# Wio_Node_v1_0.net
KiCad netlist of a schematic drawn in EAGLE
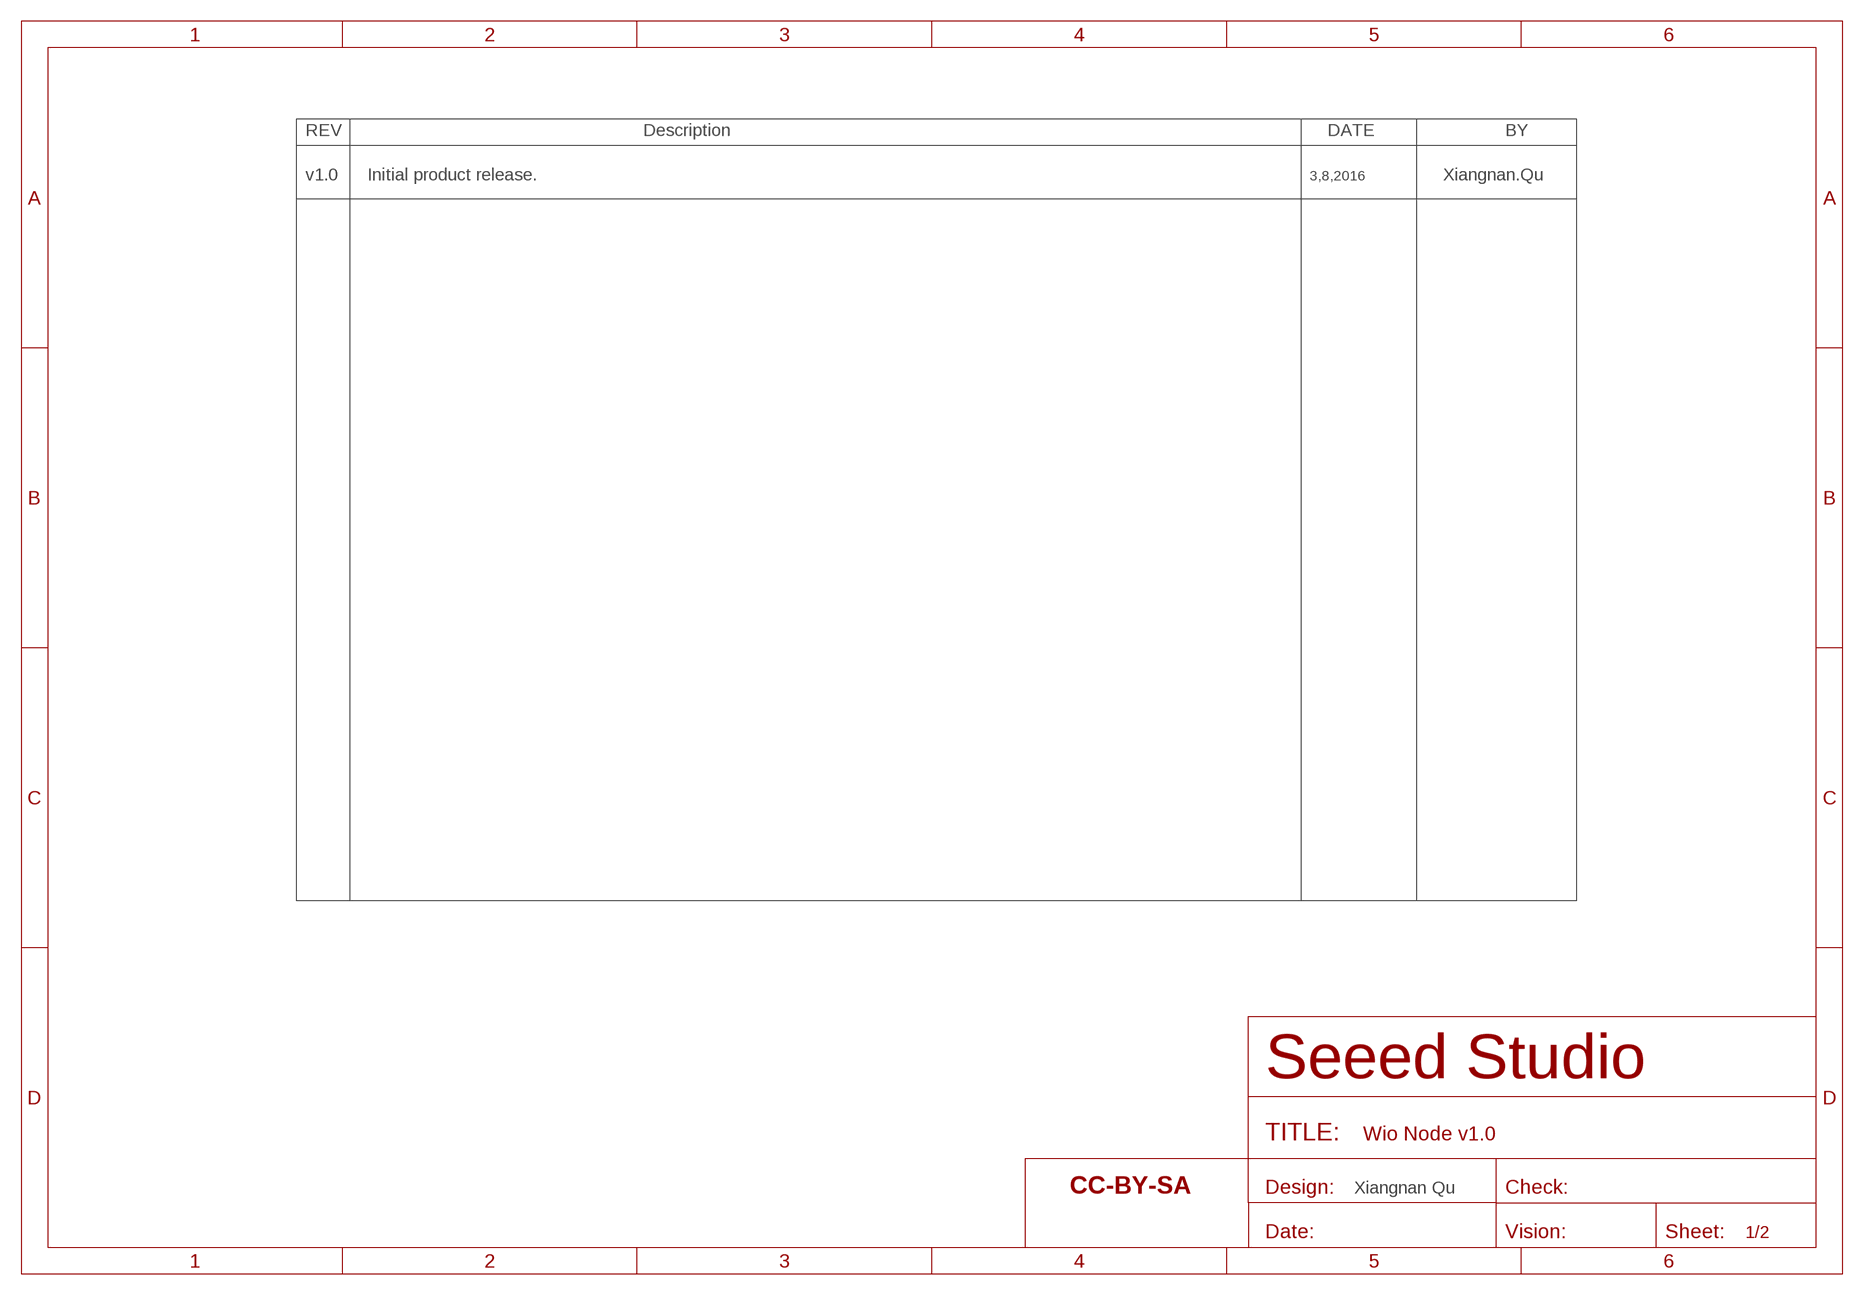
[diagram p0: schematic, sheet 1]
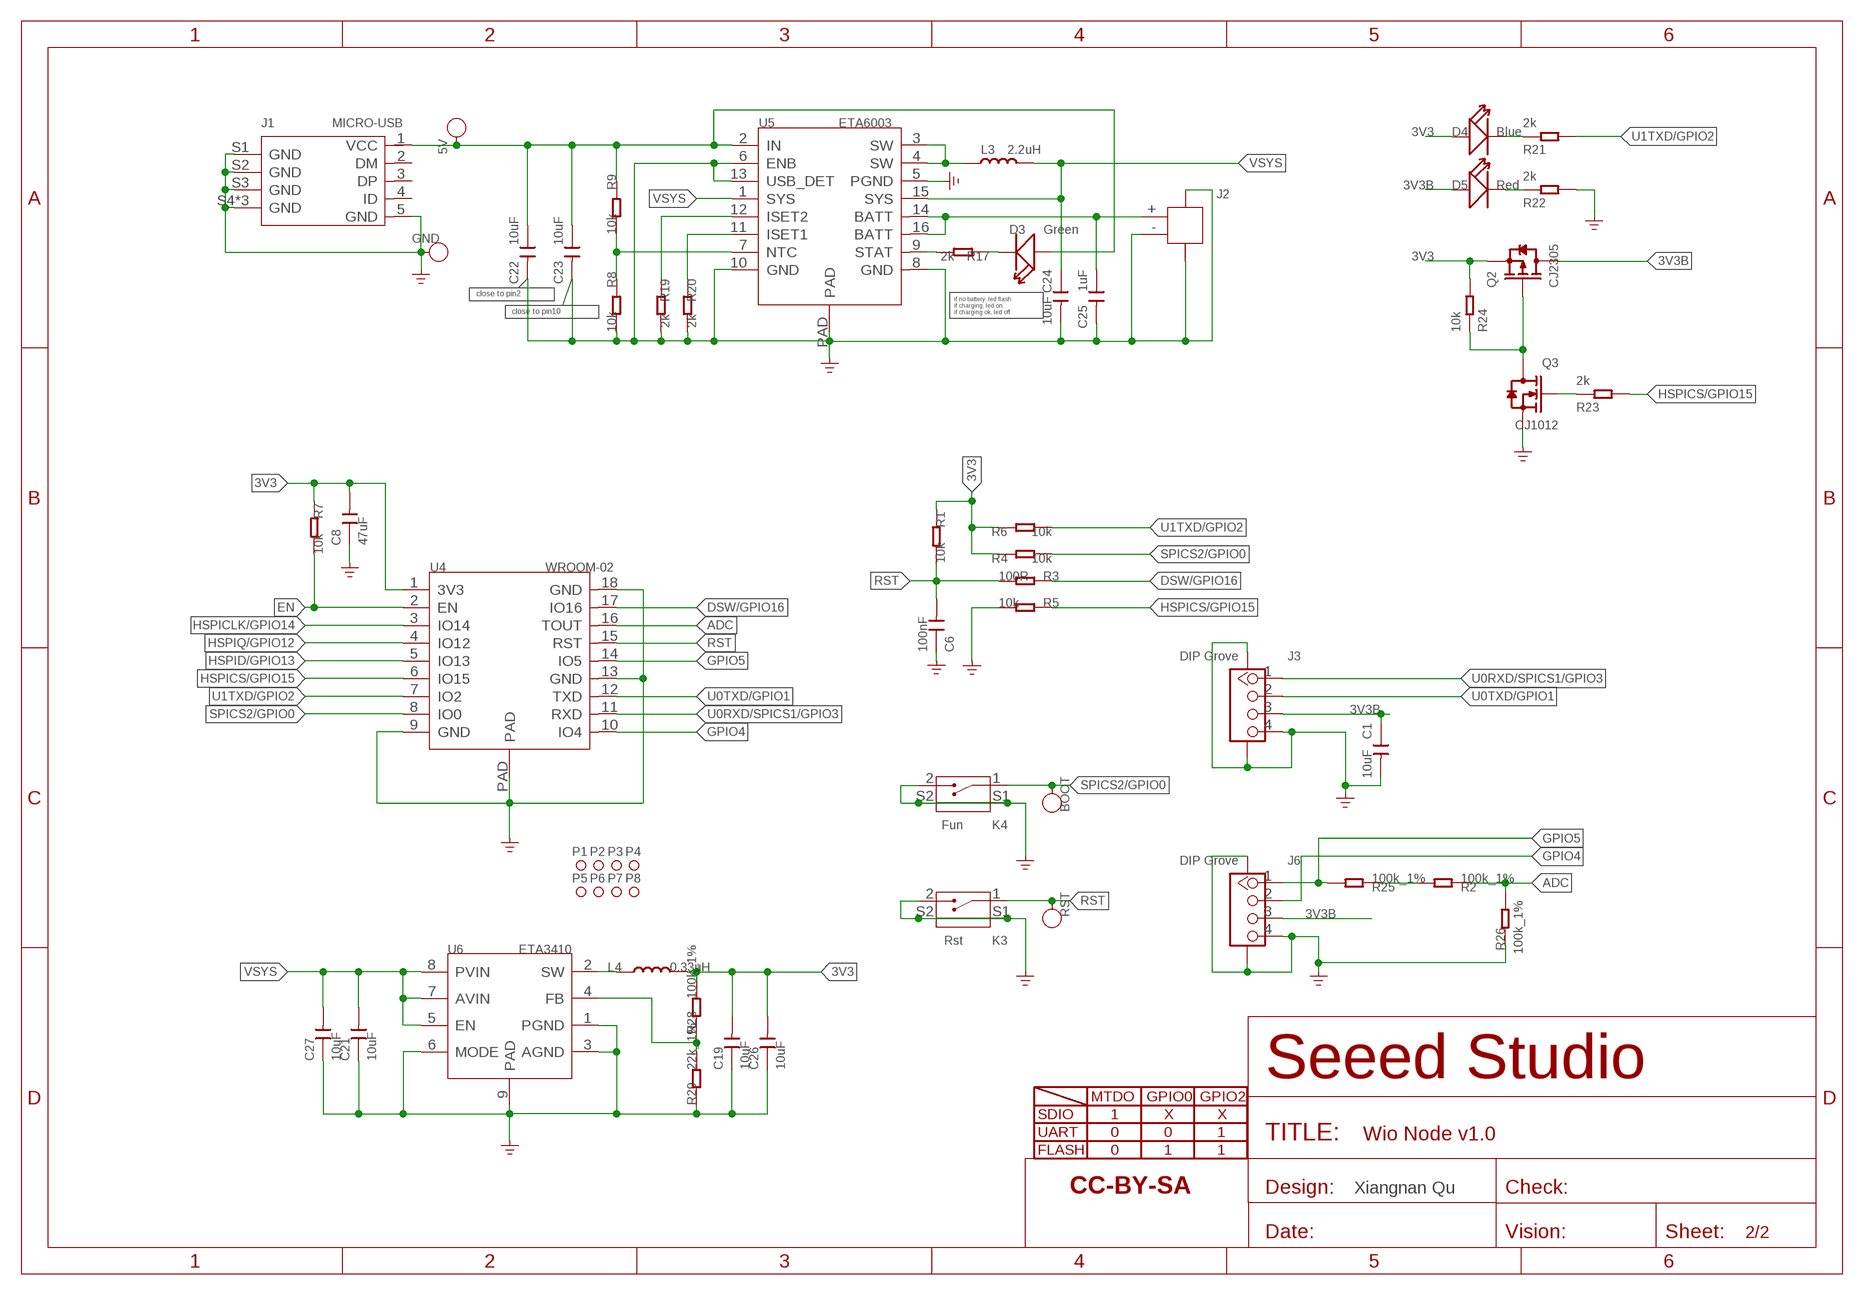
[diagram p1: schematic, sheet 2]

(export (version "E")
  (design (tool "Eeschema 10.0.6"))
  (components
    (comp (ref "5V")
      (value "TEST-POINT'4545'")
      (footprint "eagle-import:TP-D45MIL")
      (fields (field (name "PARTNO") "DNP"))
      (libsource (lib "eagle-import") (part "TEST-POINT'4545'"))
    )
    (comp (ref "BOOT")
      (value "TEST-POINT'4545'")
      (footprint "eagle-import:TP-D45MIL")
      (fields (field (name "PARTNO") "DNP"))
      (libsource (lib "eagle-import") (part "TEST-POINT'4545'"))
    )
    (comp (ref "C1")
      (value "10uF")
      (footprint "eagle-import:C0402")
      (libsource (lib "eagle-import") (part "CAP-0402"))
    )
    (comp (ref "C6")
      (value "100nF")
      (footprint "eagle-import:C0201")
      (libsource (lib "eagle-import") (part "CAP-0201"))
    )
    (comp (ref "C8")
      (value "47uF")
      (footprint "eagle-import:C0805")
      (libsource (lib "eagle-import") (part "CAP-0805"))
    )
    (comp (ref "C19")
      (value "10uF")
      (footprint "eagle-import:C0402")
      (libsource (lib "eagle-import") (part "CAP-0402"))
    )
    (comp (ref "C21")
      (value "10uF")
      (footprint "eagle-import:C0402")
      (libsource (lib "eagle-import") (part "CAP-0402"))
    )
    (comp (ref "C22")
      (value "10uF")
      (footprint "eagle-import:C0805")
      (libsource (lib "eagle-import") (part "CAP-0805"))
    )
    (comp (ref "C23")
      (value "10uF")
      (footprint "eagle-import:C0402")
      (libsource (lib "eagle-import") (part "CAP-0402"))
    )
    (comp (ref "C24")
      (value "10uF")
      (footprint "eagle-import:C0402")
      (libsource (lib "eagle-import") (part "CAP-0402"))
    )
    (comp (ref "C25")
      (value "1uF")
      (footprint "eagle-import:C0402")
      (libsource (lib "eagle-import") (part "CAP-0402"))
    )
    (comp (ref "C26")
      (value "10uF")
      (footprint "eagle-import:C0402")
      (libsource (lib "eagle-import") (part "CAP-0402"))
    )
    (comp (ref "C27")
      (value "10uF")
      (footprint "eagle-import:C0402")
      (libsource (lib "eagle-import") (part "CAP-0402"))
    )
    (comp (ref "D3")
      (value "Green")
      (footprint "eagle-import:LED-0402")
      (libsource (lib "eagle-import") (part "LED-0402"))
    )
    (comp (ref "D4")
      (value "Blue")
      (footprint "eagle-import:LED-0402")
      (libsource (lib "eagle-import") (part "LED-0402"))
    )
    (comp (ref "D5")
      (value "Red")
      (footprint "eagle-import:LED-0402")
      (libsource (lib "eagle-import") (part "LED-0402"))
    )
    (comp (ref "FR1")
      (value "SEEEDSTUDIO-OPEN-SCH-FRAME")
      (footprint "eagle-import:SEEEDSTUDIO-PCB-FRAME")
      (libsource (lib "eagle-import") (part "SEEEDSTUDIO-OPEN-SCH-FRAME"))
    )
    (comp (ref "GND")
      (value "TEST-POINT'4545'")
      (footprint "eagle-import:TP-D45MIL")
      (fields (field (name "PARTNO") "DNP"))
      (libsource (lib "eagle-import") (part "TEST-POINT'4545'"))
    )
    (comp (ref "J1")
      (value "MICRO-USB")
      (footprint "eagle-import:MICRO-USB5+4P-SMD-0.65-B")
      (libsource (lib "eagle-import") (part "MICRO-USB5+4P'5+4P'"))
    )
    (comp (ref "J2")
      (value "JST-2P-SMD'2.0'")
      (footprint "eagle-import:HW2-SMD-2.0-90D")
      (libsource (lib "eagle-import") (part "JST-2P-SMD'2.0'"))
    )
    (comp (ref "J3")
      (value "DIP Grove")
      (footprint "eagle-import:HW4-SMD-2.0-90D")
      (libsource (lib "eagle-import") (part "GROVE-CONNECTOR-SMD'90D'"))
    )
    (comp (ref "J6")
      (value "DIP Grove")
      (footprint "eagle-import:HW4-SMD-2.0-90D")
      (libsource (lib "eagle-import") (part "GROVE-CONNECTOR-SMD'90D'"))
    )
    (comp (ref "K3")
      (value "Rst")
      (footprint "eagle-import:SW4-SMD-4.5X3.8X1.8MM-90D")
      (libsource (lib "eagle-import") (part "BUTTON-2+2P'HQ-TP-1100A'"))
    )
    (comp (ref "K4")
      (value "Fun")
      (footprint "eagle-import:SW4-SMD-4.5X3.8X1.8MM-90D")
      (libsource (lib "eagle-import") (part "BUTTON-2+2P'HQ-TP-1100A'"))
    )
    (comp (ref "L3")
      (value "2.2uH")
      (footprint "eagle-import:L0805")
      (libsource (lib "eagle-import") (part "INDUCTOR/FERRITE-BEAD'0805'"))
    )
    (comp (ref "L4")
      (value "0.33uH")
      (footprint "eagle-import:L201610")
      (libsource (lib "eagle-import") (part "L-MPM201610SR33_T"))
    )
    (comp (ref "P1")
      (value "MARK-1.0'ANNULAR'")
      (footprint "eagle-import:ROUND-MARK-1.0")
      (fields (field (name "PARTNO") "DNP"))
      (libsource (lib "eagle-import") (part "MARK-1.0'ANNULAR'"))
    )
    (comp (ref "P2")
      (value "MARK-1.0'ANNULAR'")
      (footprint "eagle-import:ROUND-MARK-1.0")
      (fields (field (name "PARTNO") "DNP"))
      (libsource (lib "eagle-import") (part "MARK-1.0'ANNULAR'"))
    )
    (comp (ref "P3")
      (value "MARK-1.0'ANNULAR'")
      (footprint "eagle-import:ROUND-MARK-1.0")
      (fields (field (name "PARTNO") "DNP"))
      (libsource (lib "eagle-import") (part "MARK-1.0'ANNULAR'"))
    )
    (comp (ref "P4")
      (value "MARK-1.0'ANNULAR'")
      (footprint "eagle-import:ROUND-MARK-1.0")
      (fields (field (name "PARTNO") "DNP"))
      (libsource (lib "eagle-import") (part "MARK-1.0'ANNULAR'"))
    )
    (comp (ref "P5")
      (value "MARK-1.0'ANNULAR'")
      (footprint "eagle-import:ROUND-MARK-1.0")
      (fields (field (name "PARTNO") "DNP"))
      (libsource (lib "eagle-import") (part "MARK-1.0'ANNULAR'"))
    )
    (comp (ref "P6")
      (value "MARK-1.0'ANNULAR'")
      (footprint "eagle-import:ROUND-MARK-1.0")
      (fields (field (name "PARTNO") "DNP"))
      (libsource (lib "eagle-import") (part "MARK-1.0'ANNULAR'"))
    )
    (comp (ref "P7")
      (value "MARK-1.0'ANNULAR'")
      (footprint "eagle-import:ROUND-MARK-1.0")
      (fields (field (name "PARTNO") "DNP"))
      (libsource (lib "eagle-import") (part "MARK-1.0'ANNULAR'"))
    )
    (comp (ref "P8")
      (value "MARK-1.0'ANNULAR'")
      (footprint "eagle-import:ROUND-MARK-1.0")
      (fields (field (name "PARTNO") "DNP"))
      (libsource (lib "eagle-import") (part "MARK-1.0'ANNULAR'"))
    )
    (comp (ref "Q2")
      (value "CJ2305")
      (footprint "eagle-import:SOT-23")
      (libsource (lib "eagle-import") (part "MOSFET-P'SI2323CDS/SI2305DS{lt}BR{gt}'"))
    )
    (comp (ref "Q3")
      (value "CJ1012")
      (footprint "eagle-import:SOT-523")
      (libsource (lib "eagle-import") (part "MOSFET-N+"))
    )
    (comp (ref "R1")
      (value "10k")
      (footprint "eagle-import:R0201")
      (libsource (lib "eagle-import") (part "RES-0201"))
    )
    (comp (ref "R2")
      (value "100k_1%")
      (footprint "eagle-import:R0201")
      (libsource (lib "eagle-import") (part "RES-0201"))
    )
    (comp (ref "R3")
      (value "100R")
      (footprint "eagle-import:R0201")
      (libsource (lib "eagle-import") (part "RES-0201"))
    )
    (comp (ref "R4")
      (value "10k")
      (footprint "eagle-import:R0201")
      (libsource (lib "eagle-import") (part "RES-0201"))
    )
    (comp (ref "R5")
      (value "10k")
      (footprint "eagle-import:R0201")
      (libsource (lib "eagle-import") (part "RES-0201"))
    )
    (comp (ref "R6")
      (value "10k")
      (footprint "eagle-import:R0201")
      (libsource (lib "eagle-import") (part "RES-0201"))
    )
    (comp (ref "R7")
      (value "10k")
      (footprint "eagle-import:R0201")
      (libsource (lib "eagle-import") (part "RES-0201"))
    )
    (comp (ref "R8")
      (value "10k")
      (footprint "eagle-import:R0201")
      (libsource (lib "eagle-import") (part "RES-0201"))
    )
    (comp (ref "R9")
      (value "10k")
      (footprint "eagle-import:R0201")
      (libsource (lib "eagle-import") (part "RES-0201"))
    )
    (comp (ref "R17")
      (value "2k")
      (footprint "eagle-import:R0201")
      (libsource (lib "eagle-import") (part "RES-0201"))
    )
    (comp (ref "R19")
      (value "2k")
      (footprint "eagle-import:R0201")
      (libsource (lib "eagle-import") (part "RES-0201"))
    )
    (comp (ref "R20")
      (value "2k")
      (footprint "eagle-import:R0201")
      (libsource (lib "eagle-import") (part "RES-0201"))
    )
    (comp (ref "R21")
      (value "2k")
      (footprint "eagle-import:R0201")
      (libsource (lib "eagle-import") (part "RES-0201"))
    )
    (comp (ref "R22")
      (value "2k")
      (footprint "eagle-import:R0201")
      (libsource (lib "eagle-import") (part "RES-0201"))
    )
    (comp (ref "R23")
      (value "2k")
      (footprint "eagle-import:R0201")
      (libsource (lib "eagle-import") (part "RES-0201"))
    )
    (comp (ref "R24")
      (value "10k")
      (footprint "eagle-import:R0201")
      (libsource (lib "eagle-import") (part "RES-0201"))
    )
    (comp (ref "R25")
      (value "100k_1%")
      (footprint "eagle-import:R0201")
      (libsource (lib "eagle-import") (part "RES-0201"))
    )
    (comp (ref "R26")
      (value "100k_1%")
      (footprint "eagle-import:R0201")
      (libsource (lib "eagle-import") (part "RES-0201"))
    )
    (comp (ref "R28")
      (value "100k_1%")
      (footprint "eagle-import:R0201")
      (libsource (lib "eagle-import") (part "RES-0201"))
    )
    (comp (ref "R29")
      (value "22k_1%")
      (footprint "eagle-import:R0402")
      (libsource (lib "eagle-import") (part "RES-0402"))
    )
    (comp (ref "RST")
      (value "TEST-POINT'4545'")
      (footprint "eagle-import:TP-D45MIL")
      (fields (field (name "PARTNO") "DNP"))
      (libsource (lib "eagle-import") (part "TEST-POINT'4545'"))
    )
    (comp (ref "U4")
      (value "WROOM-02")
      (footprint "eagle-import:ESP18-SMD-1.5-18X20MM")
      (libsource (lib "eagle-import") (part "MOUDLE-WIFI-ESP-WROOM-02"))
    )
    (comp (ref "U5")
      (value "ETA6003")
      (footprint "eagle-import:QFN16G-0.5-3X3MM")
      (libsource (lib "eagle-import") (part "PMIC-ETA6003"))
    )
    (comp (ref "U6")
      (value "ETA3410")
      (footprint "eagle-import:DFN8G-0.5-2X2MM")
      (libsource (lib "eagle-import") (part "CONVERTER-ETA3410"))
    )
    (comp (ref "FR4")
      (value "SEEEDSTUDIO-OPEN-SCH-FRAME")
      (footprint "eagle-import:SEEEDSTUDIO-PCB-FRAME")
      (libsource (lib "eagle-import") (part "SEEEDSTUDIO-OPEN-SCH-FRAME"))
    )
  )
  (nets
    (net (code "1") (name "3V3") (class "Default")
      (node (ref "C19") (pin "2") (pinfunction "2_2") (pintype "passive"))
      (node (ref "C26") (pin "2") (pinfunction "2_2") (pintype "passive"))
      (node (ref "C8") (pin "2") (pinfunction "2_2") (pintype "passive"))
      (node (ref "D4") (pin "+") (pinfunction "+_+") (pintype "passive"))
      (node (ref "L4") (pin "2") (pinfunction "2_2") (pintype "passive"))
      (node (ref "Q2") (pin "2") (pinfunction "S_2") (pintype "passive"))
      (node (ref "R1") (pin "1") (pinfunction "1_1") (pintype "passive"))
      (node (ref "R24") (pin "2") (pinfunction "2_2") (pintype "passive"))
      (node (ref "R28") (pin "2") (pinfunction "2_2") (pintype "passive"))
      (node (ref "R4") (pin "1") (pinfunction "1_1") (pintype "passive"))
      (node (ref "R6") (pin "1") (pinfunction "1_1") (pintype "passive"))
      (node (ref "R7") (pin "1") (pinfunction "1_1") (pintype "passive"))
      (node (ref "U4") (pin "1") (pinfunction "3V3_1") (pintype "bidirectional"))
    )
    (net (code "2") (name "3V3B") (class "Default")
      (node (ref "C1") (pin "1") (pinfunction "1_1") (pintype "passive"))
      (node (ref "D5") (pin "+") (pinfunction "+_+") (pintype "passive"))
      (node (ref "J3") (pin "3") (pinfunction "3_3") (pintype "bidirectional"))
      (node (ref "J6") (pin "3") (pinfunction "3_3") (pintype "bidirectional"))
      (node (ref "Q2") (pin "3") (pinfunction "D_3") (pintype "passive"))
    )
    (net (code "3") (name "ADC") (class "Default")
      (node (ref "R2") (pin "1") (pinfunction "1_1") (pintype "passive"))
      (node (ref "R26") (pin "2") (pinfunction "2_2") (pintype "passive"))
      (node (ref "U4") (pin "16") (pinfunction "TOUT_16") (pintype "bidirectional"))
    )
    (net (code "4") (name "DSW{slash}GPIO16") (class "Default")
      (node (ref "R3") (pin "1") (pinfunction "1_1") (pintype "passive"))
      (node (ref "U4") (pin "17") (pinfunction "IO16_17") (pintype "bidirectional"))
    )
    (net (code "5") (name "EN") (class "Default")
      (node (ref "R7") (pin "2") (pinfunction "2_2") (pintype "passive"))
      (node (ref "U4") (pin "2") (pinfunction "EN_2") (pintype "bidirectional"))
    )
    (net (code "6") (name "GND") (class "Default")
      (node (ref "C1") (pin "2") (pinfunction "2_2") (pintype "passive"))
      (node (ref "C19") (pin "1") (pinfunction "1_1") (pintype "passive"))
      (node (ref "C21") (pin "1") (pinfunction "1_1") (pintype "passive"))
      (node (ref "C22") (pin "2") (pinfunction "2_2") (pintype "passive"))
      (node (ref "C23") (pin "2") (pinfunction "2_2") (pintype "passive"))
      (node (ref "C24") (pin "2") (pinfunction "2_2") (pintype "passive"))
      (node (ref "C25") (pin "2") (pinfunction "2_2") (pintype "passive"))
      (node (ref "C26") (pin "1") (pinfunction "1_1") (pintype "passive"))
      (node (ref "C27") (pin "1") (pinfunction "1_1") (pintype "passive"))
      (node (ref "C6") (pin "1") (pinfunction "1_1") (pintype "passive"))
      (node (ref "C8") (pin "1") (pinfunction "1_1") (pintype "passive"))
      (node (ref "GND") (pin "T") (pinfunction "T_T") (pintype "bidirectional"))
      (node (ref "J1") (pin "5") (pinfunction "GND_5") (pintype "bidirectional"))
      (node (ref "J1") (pin "S1") (pinfunction "GND_S1") (pintype "bidirectional"))
      (node (ref "J1") (pin "S2") (pinfunction "GND_S2") (pintype "bidirectional"))
      (node (ref "J1") (pin "S3") (pinfunction "GND_S3") (pintype "bidirectional"))
      (node (ref "J1") (pin "S4") (pinfunction "GND_S4") (pintype "bidirectional"))
      (node (ref "J1") (pin "S5") (pinfunction "GND_S5") (pintype "bidirectional"))
      (node (ref "J1") (pin "S6") (pinfunction "GND_S6") (pintype "bidirectional"))
      (node (ref "J2") (pin "-") (pinfunction "2_-") (pintype "bidirectional"))
      (node (ref "J2") (pin "3") (pinfunction "3_3") (pintype "bidirectional"))
      (node (ref "J2") (pin "4") (pinfunction "4_4") (pintype "bidirectional"))
      (node (ref "J3") (pin "4") (pinfunction "4_4") (pintype "bidirectional"))
      (node (ref "J3") (pin "SS1") (pinfunction "SS1_SS1") (pintype "bidirectional"))
      (node (ref "J3") (pin "SS2") (pinfunction "SS2_SS2") (pintype "bidirectional"))
      (node (ref "J6") (pin "4") (pinfunction "4_4") (pintype "bidirectional"))
      (node (ref "J6") (pin "SS1") (pinfunction "SS1_SS1") (pintype "bidirectional"))
      (node (ref "J6") (pin "SS2") (pinfunction "SS2_SS2") (pintype "bidirectional"))
      (node (ref "K3") (pin "2") (pinfunction "2_2") (pintype "bidirectional"))
      (node (ref "K3") (pin "S1") (pinfunction "S1_S1") (pintype "bidirectional"))
      (node (ref "K3") (pin "S2") (pinfunction "S2_S2") (pintype "bidirectional"))
      (node (ref "K4") (pin "2") (pinfunction "2_2") (pintype "bidirectional"))
      (node (ref "K4") (pin "S1") (pinfunction "S1_S1") (pintype "bidirectional"))
      (node (ref "K4") (pin "S2") (pinfunction "S2_S2") (pintype "bidirectional"))
      (node (ref "Q3") (pin "2") (pinfunction "S_2") (pintype "passive"))
      (node (ref "R19") (pin "2") (pinfunction "2_2") (pintype "passive"))
      (node (ref "R20") (pin "2") (pinfunction "2_2") (pintype "passive"))
      (node (ref "R22") (pin "2") (pinfunction "2_2") (pintype "passive"))
      (node (ref "R26") (pin "1") (pinfunction "1_1") (pintype "passive"))
      (node (ref "R29") (pin "1") (pinfunction "1_1") (pintype "passive"))
      (node (ref "R5") (pin "2") (pinfunction "2_2") (pintype "passive"))
      (node (ref "R8") (pin "2") (pinfunction "2_2") (pintype "passive"))
      (node (ref "U4") (pin "13") (pinfunction "GND_13") (pintype "bidirectional"))
      (node (ref "U4") (pin "18") (pinfunction "GND_18") (pintype "bidirectional"))
      (node (ref "U4") (pin "9") (pinfunction "GND_9") (pintype "bidirectional"))
      (node (ref "U4") (pin "PAD") (pinfunction "PAD_PAD") (pintype "bidirectional"))
      (node (ref "U5") (pin "10") (pinfunction "GND_10") (pintype "bidirectional"))
      (node (ref "U5") (pin "13") (pinfunction "USB_DET_13") (pintype "bidirectional"))
      (node (ref "U5") (pin "5") (pinfunction "PGND_5") (pintype "bidirectional"))
      (node (ref "U5") (pin "6") (pinfunction "ENB_6") (pintype "bidirectional"))
      (node (ref "U5") (pin "8") (pinfunction "GND_8") (pintype "bidirectional"))
      (node (ref "U5") (pin "PAD") (pinfunction "PAD_PAD") (pintype "bidirectional"))
      (node (ref "U6") (pin "1") (pinfunction "PGND_1") (pintype "bidirectional"))
      (node (ref "U6") (pin "3") (pinfunction "AGND_3") (pintype "bidirectional"))
      (node (ref "U6") (pin "6") (pinfunction "MODE_6") (pintype "bidirectional"))
      (node (ref "U6") (pin "9") (pinfunction "PAD_9") (pintype "bidirectional"))
    )
    (net (code "7") (name "GPIO4") (class "Default")
      (node (ref "J6") (pin "2") (pinfunction "2_2") (pintype "bidirectional"))
      (node (ref "U4") (pin "10") (pinfunction "IO4_10") (pintype "bidirectional"))
    )
    (net (code "8") (name "GPIO5") (class "Default")
      (node (ref "J6") (pin "1") (pinfunction "1_1") (pintype "bidirectional"))
      (node (ref "R25") (pin "2") (pinfunction "2_2") (pintype "passive"))
      (node (ref "U4") (pin "14") (pinfunction "IO5_14") (pintype "bidirectional"))
    )
    (net (code "9") (name "HSPICLK{slash}GPIO14") (class "Default")
      (node (ref "U4") (pin "3") (pinfunction "IO14_3") (pintype "bidirectional"))
    )
    (net (code "10") (name "HSPICS{slash}GPIO15") (class "Default")
      (node (ref "R23") (pin "2") (pinfunction "2_2") (pintype "passive"))
      (node (ref "R5") (pin "1") (pinfunction "1_1") (pintype "passive"))
      (node (ref "U4") (pin "6") (pinfunction "IO15_6") (pintype "bidirectional"))
    )
    (net (code "11") (name "HSPID{slash}GPIO13") (class "Default")
      (node (ref "U4") (pin "5") (pinfunction "IO13_5") (pintype "bidirectional"))
    )
    (net (code "12") (name "HSPIQ{slash}GPIO12") (class "Default")
      (node (ref "U4") (pin "4") (pinfunction "IO12_4") (pintype "bidirectional"))
    )
    (net (code "13") (name "Net-(D3-Pad-)") (class "Default")
      (node (ref "D3") (pin "-") (pinfunction "-_-") (pintype "passive"))
      (node (ref "R17") (pin "1") (pinfunction "1_1") (pintype "passive"))
    )
    (net (code "14") (name "Net-(D4-Pad-)") (class "Default")
      (node (ref "D4") (pin "-") (pinfunction "-_-") (pintype "passive"))
      (node (ref "R21") (pin "1") (pinfunction "1_1") (pintype "passive"))
    )
    (net (code "15") (name "Net-(D5-Pad-)") (class "Default")
      (node (ref "D5") (pin "-") (pinfunction "-_-") (pintype "passive"))
      (node (ref "R22") (pin "1") (pinfunction "1_1") (pintype "passive"))
    )
    (net (code "16") (name "Net-(J1-VCC)") (class "Default")
      (node (ref "5V") (pin "T") (pinfunction "T_T") (pintype "bidirectional"))
      (node (ref "C22") (pin "1") (pinfunction "1_1") (pintype "passive"))
      (node (ref "C23") (pin "1") (pinfunction "1_1") (pintype "passive"))
      (node (ref "D3") (pin "+") (pinfunction "+_+") (pintype "passive"))
      (node (ref "J1") (pin "1") (pinfunction "VCC_1") (pintype "bidirectional"))
      (node (ref "R9") (pin "1") (pinfunction "1_1") (pintype "passive"))
      (node (ref "U5") (pin "2") (pinfunction "IN_2") (pintype "bidirectional"))
    )
    (net (code "17") (name "Net-(J2-1)") (class "Default")
      (node (ref "C25") (pin "1") (pinfunction "1_1") (pintype "passive"))
      (node (ref "J2") (pin "+") (pinfunction "1_+") (pintype "bidirectional"))
      (node (ref "U5") (pin "14") (pinfunction "BATT_14") (pintype "bidirectional"))
      (node (ref "U5") (pin "16") (pinfunction "BATT_16") (pintype "bidirectional"))
    )
    (net (code "18") (name "Net-(L3-Pad1)") (class "Default")
      (node (ref "L3") (pin "1") (pinfunction "1_1") (pintype "passive"))
      (node (ref "U5") (pin "3") (pinfunction "SW_3") (pintype "bidirectional"))
      (node (ref "U5") (pin "4") (pinfunction "SW_4") (pintype "bidirectional"))
    )
    (net (code "19") (name "Net-(Q2-G)") (class "Default")
      (node (ref "Q2") (pin "1") (pinfunction "G_1") (pintype "passive"))
      (node (ref "Q3") (pin "3") (pinfunction "D_3") (pintype "passive"))
      (node (ref "R24") (pin "1") (pinfunction "1_1") (pintype "passive"))
    )
    (net (code "20") (name "Net-(Q3-G)") (class "Default")
      (node (ref "Q3") (pin "1") (pinfunction "G_1") (pintype "passive"))
      (node (ref "R23") (pin "1") (pinfunction "1_1") (pintype "passive"))
    )
    (net (code "21") (name "Net-(R2-Pad2)") (class "Default")
      (node (ref "R2") (pin "2") (pinfunction "2_2") (pintype "passive"))
      (node (ref "R25") (pin "1") (pinfunction "1_1") (pintype "passive"))
    )
    (net (code "22") (name "Net-(U5-ISET1)") (class "Default")
      (node (ref "R20") (pin "1") (pinfunction "1_1") (pintype "passive"))
      (node (ref "U5") (pin "11") (pinfunction "ISET1_11") (pintype "bidirectional"))
    )
    (net (code "23") (name "Net-(U5-ISET2)") (class "Default")
      (node (ref "R19") (pin "1") (pinfunction "1_1") (pintype "passive"))
      (node (ref "U5") (pin "12") (pinfunction "ISET2_12") (pintype "bidirectional"))
    )
    (net (code "24") (name "Net-(U5-NTC)") (class "Default")
      (node (ref "R8") (pin "1") (pinfunction "1_1") (pintype "passive"))
      (node (ref "R9") (pin "2") (pinfunction "2_2") (pintype "passive"))
      (node (ref "U5") (pin "7") (pinfunction "NTC_7") (pintype "bidirectional"))
    )
    (net (code "25") (name "Net-(U5-STAT)") (class "Default")
      (node (ref "R17") (pin "2") (pinfunction "2_2") (pintype "passive"))
      (node (ref "U5") (pin "9") (pinfunction "STAT_9") (pintype "bidirectional"))
    )
    (net (code "26") (name "Net-(U6-FB)") (class "Default")
      (node (ref "R28") (pin "1") (pinfunction "1_1") (pintype "passive"))
      (node (ref "R29") (pin "2") (pinfunction "2_2") (pintype "passive"))
      (node (ref "U6") (pin "4") (pinfunction "FB_4") (pintype "bidirectional"))
    )
    (net (code "27") (name "Net-(U6-SW)") (class "Default")
      (node (ref "L4") (pin "1") (pinfunction "1_1") (pintype "passive"))
      (node (ref "U6") (pin "2") (pinfunction "SW_2") (pintype "bidirectional"))
    )
    (net (code "28") (name "RST") (class "Default")
      (node (ref "C6") (pin "2") (pinfunction "2_2") (pintype "passive"))
      (node (ref "K3") (pin "1") (pinfunction "1_1") (pintype "bidirectional"))
      (node (ref "R1") (pin "2") (pinfunction "2_2") (pintype "passive"))
      (node (ref "R3") (pin "2") (pinfunction "2_2") (pintype "passive"))
      (node (ref "RST") (pin "T") (pinfunction "T_T") (pintype "bidirectional"))
      (node (ref "U4") (pin "15") (pinfunction "RST_15") (pintype "bidirectional"))
    )
    (net (code "29") (name "SPICS2{slash}GPIO0") (class "Default")
      (node (ref "BOOT") (pin "T") (pinfunction "T_T") (pintype "bidirectional"))
      (node (ref "K4") (pin "1") (pinfunction "1_1") (pintype "bidirectional"))
      (node (ref "R4") (pin "2") (pinfunction "2_2") (pintype "passive"))
      (node (ref "U4") (pin "8") (pinfunction "IO0_8") (pintype "bidirectional"))
    )
    (net (code "30") (name "U0RXD{slash}SPICS1{slash}GPIO3") (class "Default")
      (node (ref "J3") (pin "1") (pinfunction "1_1") (pintype "bidirectional"))
      (node (ref "U4") (pin "11") (pinfunction "RXD_11") (pintype "bidirectional"))
    )
    (net (code "31") (name "U0TXD{slash}GPIO1") (class "Default")
      (node (ref "J3") (pin "2") (pinfunction "2_2") (pintype "bidirectional"))
      (node (ref "U4") (pin "12") (pinfunction "TXD_12") (pintype "bidirectional"))
    )
    (net (code "32") (name "U1TXD{slash}GPIO2") (class "Default")
      (node (ref "R21") (pin "2") (pinfunction "2_2") (pintype "passive"))
      (node (ref "R6") (pin "2") (pinfunction "2_2") (pintype "passive"))
      (node (ref "U4") (pin "7") (pinfunction "IO2_7") (pintype "bidirectional"))
    )
    (net (code "33") (name "VSYS") (class "Default")
      (node (ref "C21") (pin "2") (pinfunction "2_2") (pintype "passive"))
      (node (ref "C24") (pin "1") (pinfunction "1_1") (pintype "passive"))
      (node (ref "C27") (pin "2") (pinfunction "2_2") (pintype "passive"))
      (node (ref "L3") (pin "2") (pinfunction "2_2") (pintype "passive"))
      (node (ref "U5") (pin "1") (pinfunction "SYS_1") (pintype "bidirectional"))
      (node (ref "U5") (pin "15") (pinfunction "SYS_15") (pintype "bidirectional"))
      (node (ref "U6") (pin "5") (pinfunction "EN_5") (pintype "bidirectional"))
      (node (ref "U6") (pin "7") (pinfunction "AVIN_7") (pintype "bidirectional"))
      (node (ref "U6") (pin "8") (pinfunction "PVIN_8") (pintype "bidirectional"))
    )
    (net (code "34") (name "unconnected-(J1-DM-Pad2)") (class "Default")
      (node (ref "J1") (pin "2") (pinfunction "DM_2") (pintype "bidirectional"))
    )
    (net (code "35") (name "unconnected-(J1-DP-Pad3)") (class "Default")
      (node (ref "J1") (pin "3") (pinfunction "DP_3") (pintype "bidirectional"))
    )
    (net (code "36") (name "unconnected-(J1-ID-Pad4)") (class "Default")
      (node (ref "J1") (pin "4") (pinfunction "ID_4") (pintype "bidirectional"))
    )
  )
)
